# Interface_-_USB-C.net
KiCad netlist of a schematic drawn in Altium Designer
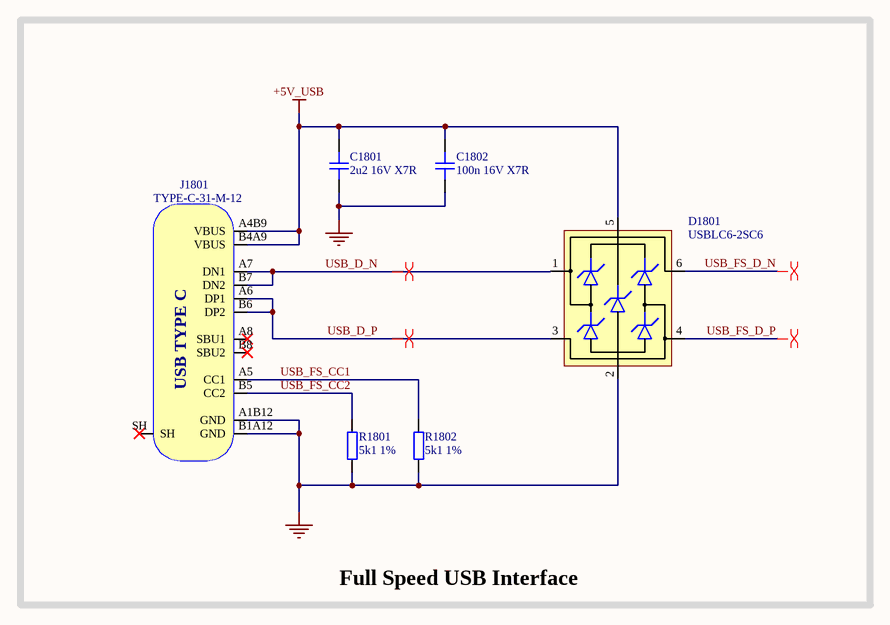
[diagram p0: Interface - USB-C.SchDoc]

(export (version "E")
  (design (tool "Eeschema 10.0.6"))
  (components
    (comp (ref "C1801")
      (value "2u2 16V X7R")
      (footprint "CAP_0603")
      (description "Capacitor SMD 0603")
      (fields
        (field (name "MANUFACTURER") "YAGEO")
        (field (name "MANUFACTURER PART NUMBER") "CC0603KRX7R7BB225")
      )
      (libsource (lib "Schematic-Lib-PhilsLab") (part "CAP_0603"))
    )
    (comp (ref "C1802")
      (value "100n 16V X7R")
      (footprint "CAP_0402")
      (description "Capacitor SMD 0402")
      (fields
        (field (name "MANUFACTURER") "YAGEO")
        (field (name "MANUFACTURER PART NUMBER") "CC0402JRX7R7BB104")
      )
      (libsource (lib "Schematic-Lib-PhilsLab") (part "CAP_0402"))
    )
    (comp (ref "D1801")
      (value "USBLC6-2SC6")
      (footprint "SOT-23-6")
      (description "Low-Capacitance ESD Protection USB")
      (fields (field (name "MANUFACTURER") "STMicroelectronics"))
      (libsource (lib "Schematic-Lib-PhilsLab") (part "USBLC6-2SC6"))
    )
    (comp (ref "J1801")
      (value "TYPE-C-31-M-12")
      (footprint "TYPE-C-31-M-12")
      (description "USB Type C Connector Horizontal SMT")
      (fields (field (name "MANUFACTURER") "Koren Hroparts"))
      (libsource (lib "Schematic-Lib-PhilsLab") (part "TYPE-C-31-M-12"))
    )
    (comp (ref "R1801")
      (value "5k1 1%")
      (footprint "RES_0402")
      (description "Resistor SMD 0402")
      (fields
        (field (name "MANUFACTURER") "PANASONIC")
        (field (name "MANUFACTURER PART NUMBER") "ERJ2GEJ512X")
      )
      (libsource (lib "Schematic-Lib-PhilsLab") (part "RES_0402"))
    )
    (comp (ref "R1802")
      (value "5k1 1%")
      (footprint "RES_0402")
      (description "Resistor SMD 0402")
      (fields
        (field (name "MANUFACTURER") "PANASONIC")
        (field (name "MANUFACTURER PART NUMBER") "ERJ2GEJ512X")
      )
      (libsource (lib "Schematic-Lib-PhilsLab") (part "RES_0402"))
    )
  )
  (nets
    (net (code "1") (name "+5V_USB") (class "Default")
      (node (ref "C1801") (pin "2") (pinfunction "2_2") (pintype "passive"))
      (node (ref "C1802") (pin "2") (pinfunction "2_2") (pintype "passive"))
      (node (ref "D1801") (pin "5") (pinfunction "VBUS_5") (pintype "power_in"))
      (node (ref "J1801") (pin "A4B9") (pinfunction "VBUS_A4B9") (pintype "power_in"))
      (node (ref "J1801") (pin "B4A9") (pinfunction "VBUS_B4A9") (pintype "power_in"))
    )
    (net (code "2") (name "/USB_D_N") (class "Default")
      (node (ref "D1801") (pin "1") (pinfunction "IO1_1") (pintype "bidirectional"))
      (node (ref "J1801") (pin "A7") (pinfunction "DN1_A7") (pintype "bidirectional"))
      (node (ref "J1801") (pin "B7") (pinfunction "DN2_B7") (pintype "bidirectional"))
    )
    (net (code "3") (name "/USB_D_P") (class "Default")
      (node (ref "D1801") (pin "3") (pinfunction "IO2_3") (pintype "bidirectional"))
      (node (ref "J1801") (pin "A6") (pinfunction "DP1_A6") (pintype "bidirectional"))
      (node (ref "J1801") (pin "B6") (pinfunction "DP2_B6") (pintype "bidirectional"))
    )
    (net (code "4") (name "/USB_FS_CC1") (class "Default")
      (node (ref "J1801") (pin "A5") (pinfunction "CC1_A5") (pintype "passive"))
      (node (ref "R1802") (pin "2") (pinfunction "2_2") (pintype "passive"))
    )
    (net (code "5") (name "/USB_FS_CC2") (class "Default")
      (node (ref "J1801") (pin "B5") (pinfunction "CC2_B5") (pintype "tri_state"))
      (node (ref "R1801") (pin "2") (pinfunction "2_2") (pintype "passive"))
    )
    (net (code "6") (name "/USB_FS_D_N") (class "Default")
      (node (ref "D1801") (pin "6") (pinfunction "IO1_6") (pintype "bidirectional"))
    )
    (net (code "7") (name "/USB_FS_D_P") (class "Default")
      (node (ref "D1801") (pin "4") (pinfunction "IO2_4") (pintype "bidirectional"))
    )
    (net (code "8") (name "GND") (class "Default")
      (node (ref "C1801") (pin "1") (pinfunction "1_1") (pintype "passive"))
      (node (ref "C1802") (pin "1") (pinfunction "1_1") (pintype "passive"))
      (node (ref "D1801") (pin "2") (pinfunction "GND_2") (pintype "power_in"))
      (node (ref "J1801") (pin "A1B12") (pinfunction "GND_A1B12") (pintype "power_in"))
      (node (ref "J1801") (pin "B1A12") (pinfunction "GND_B1A12") (pintype "power_in"))
      (node (ref "R1801") (pin "1") (pinfunction "1_1") (pintype "passive"))
      (node (ref "R1802") (pin "1") (pinfunction "1_1") (pintype "passive"))
    )
    (net (code "9") (name "unconnected-(J1801-PadSH)") (class "Default")
      (node (ref "J1801") (pin "SH") (pinfunction "SH_SH") (pintype "power_in+no_connect"))
    )
    (net (code "10") (name "unconnected-(J1801-SBU1-PadA8)") (class "Default")
      (node (ref "J1801") (pin "A8") (pinfunction "SBU1_A8") (pintype "bidirectional+no_connect"))
    )
    (net (code "11") (name "unconnected-(J1801-SBU2-PadB8)") (class "Default")
      (node (ref "J1801") (pin "B8") (pinfunction "SBU2_B8") (pintype "bidirectional+no_connect"))
    )
  )
)
